# Scheda_analogica.net
KiCad netlist of a schematic drawn in EAGLE
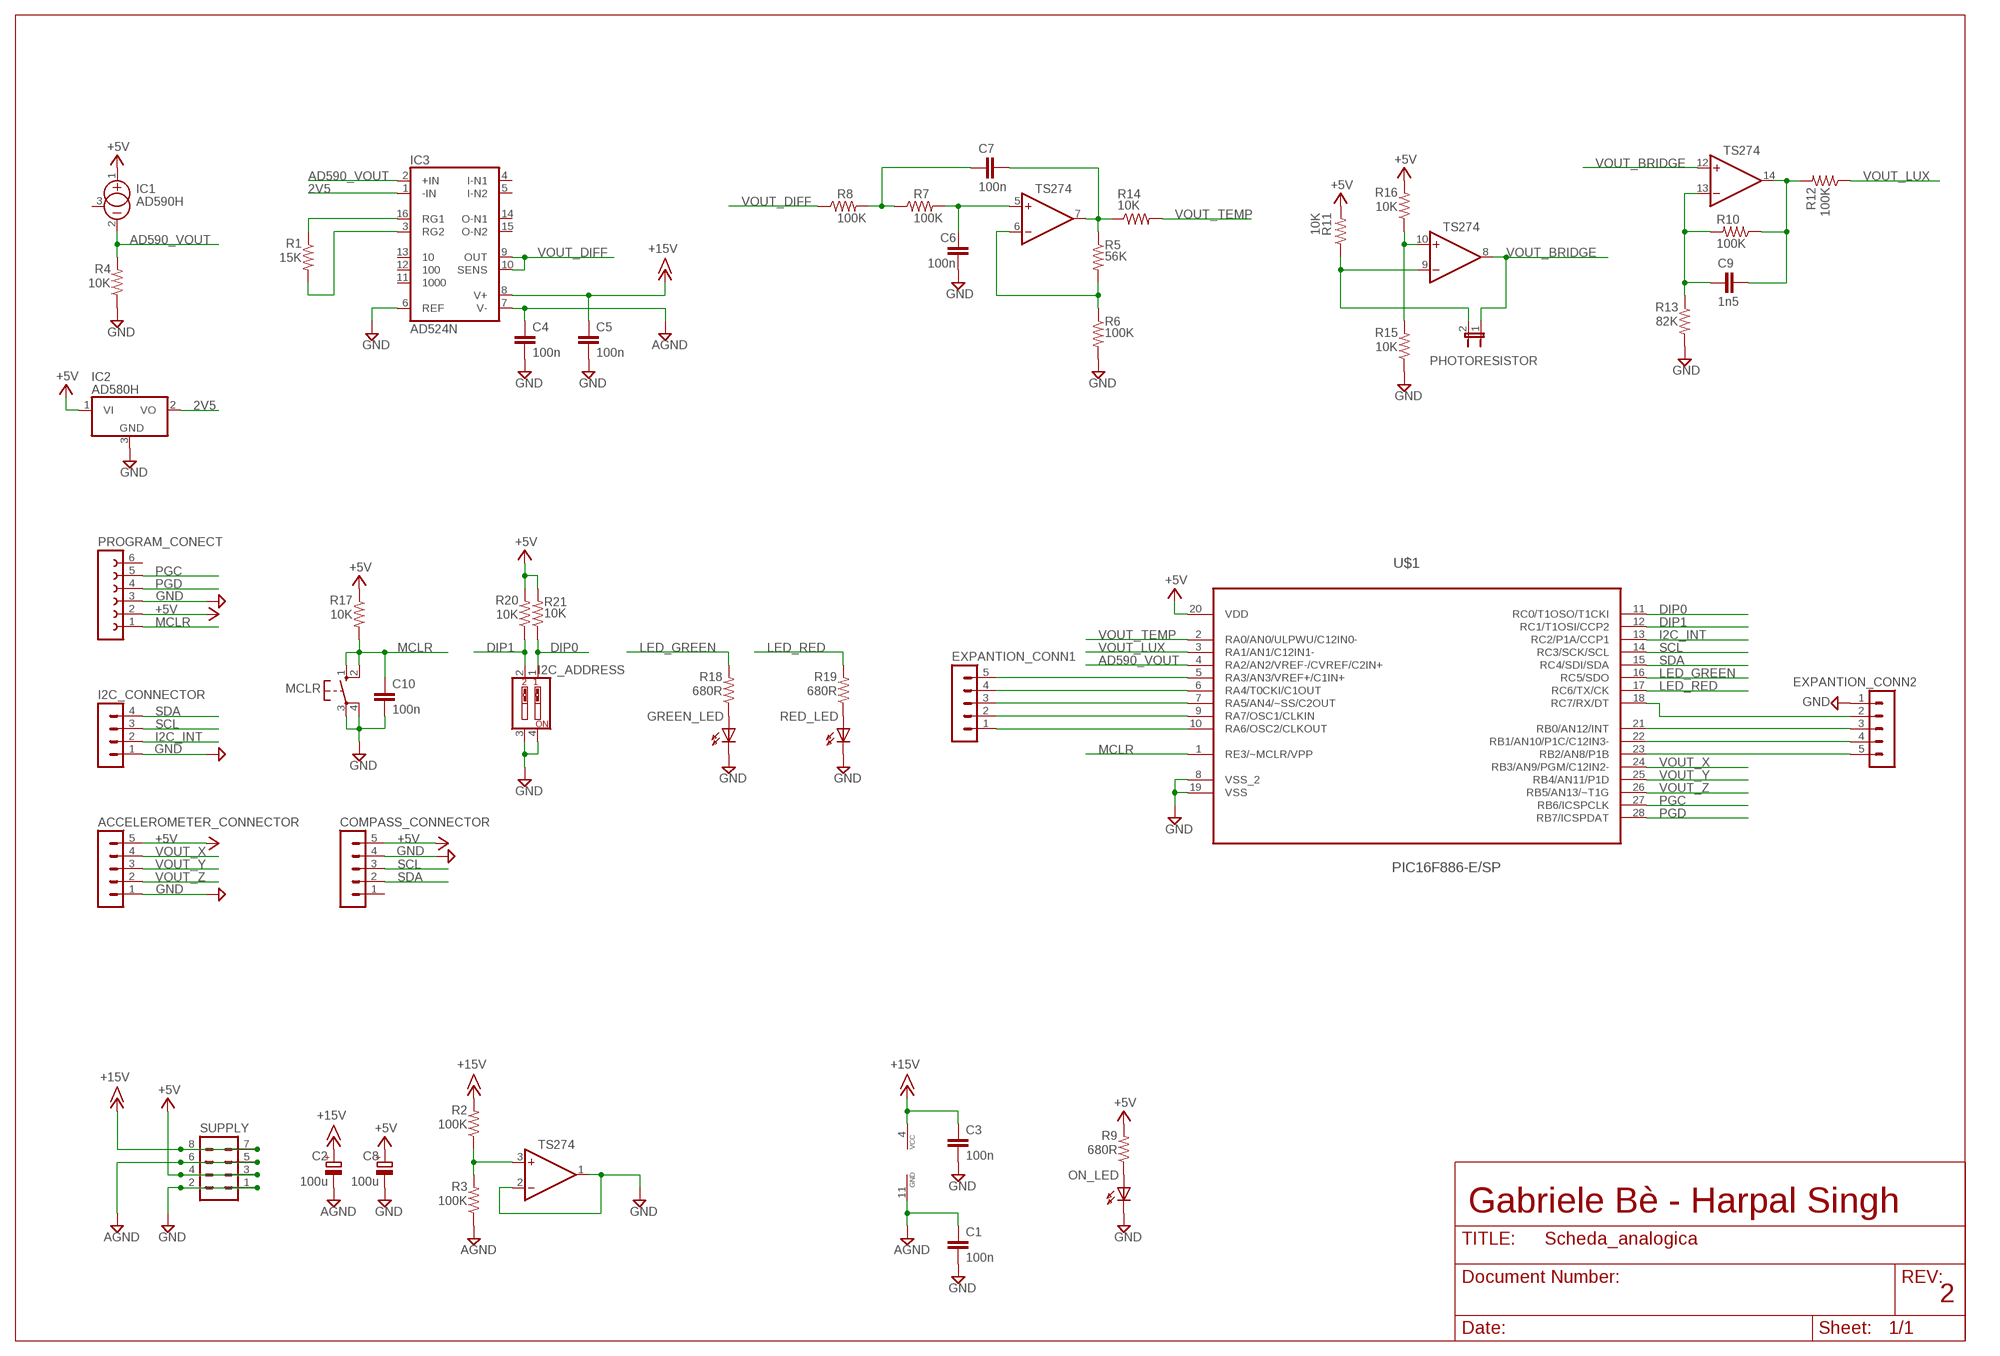
[diagram p0: schematic, sheet 1]

(export (version "E")
  (design (tool "Eeschema 10.0.6"))
  (components
    (comp (ref "ACCELEROMETER_CONNECTOR")
      (value "MA05-1")
      (footprint "eagle-import:MA05-1")
      (libsource (lib "eagle-import") (part "MA05-1"))
    )
    (comp (ref "C1")
      (value "100n")
      (footprint "eagle-import:C050-024X044")
      (libsource (lib "eagle-import") (part "C-EU050-024X044"))
    )
    (comp (ref "C2")
      (value "100u")
      (footprint "eagle-import:E2,5-7")
      (libsource (lib "eagle-import") (part "CPOL-EUE2.5-7"))
    )
    (comp (ref "C3")
      (value "100n")
      (footprint "eagle-import:C050-024X044")
      (libsource (lib "eagle-import") (part "C-EU050-024X044"))
    )
    (comp (ref "C4")
      (value "100n")
      (footprint "eagle-import:C050-024X044")
      (libsource (lib "eagle-import") (part "C-EU050-024X044"))
    )
    (comp (ref "C5")
      (value "100n")
      (footprint "eagle-import:C050-024X044")
      (libsource (lib "eagle-import") (part "C-EU050-024X044"))
    )
    (comp (ref "C6")
      (value "100n")
      (footprint "eagle-import:C050-024X044")
      (libsource (lib "eagle-import") (part "C-EU050-024X044"))
    )
    (comp (ref "C7")
      (value "100n")
      (footprint "eagle-import:C050-024X044")
      (libsource (lib "eagle-import") (part "C-EU050-024X044"))
    )
    (comp (ref "C8")
      (value "100u")
      (footprint "eagle-import:E2,5-7")
      (libsource (lib "eagle-import") (part "CPOL-EUE2.5-7"))
    )
    (comp (ref "C9")
      (value "1n5")
      (footprint "eagle-import:C050-024X044")
      (libsource (lib "eagle-import") (part "C-EU050-024X044"))
    )
    (comp (ref "C10")
      (value "100n")
      (footprint "eagle-import:C050-024X044")
      (libsource (lib "eagle-import") (part "C-EU050-024X044"))
    )
    (comp (ref "COMPASS_CONNECTOR")
      (value "MA05-1")
      (footprint "eagle-import:MA05-1")
      (libsource (lib "eagle-import") (part "MA05-1"))
    )
    (comp (ref "EXPANTION_CONN1")
      (value "MA05-1")
      (footprint "eagle-import:MA05-1")
      (libsource (lib "eagle-import") (part "MA05-1"))
    )
    (comp (ref "EXPANTION_CONN2")
      (value "MA05-1")
      (footprint "eagle-import:MA05-1")
      (libsource (lib "eagle-import") (part "MA05-1"))
    )
    (comp (ref "GREEN_LED")
      (value "HLMP6")
      (footprint "eagle-import:HLMP6")
      (fields (field (name "MF") "AGILENT TECHNOLOGIES") (field (name "MPN") "HLMP-6500"))
      (libsource (lib "eagle-import") (part "HLMP6"))
    )
    (comp (ref "I2C_ADDRESS")
      (value "SW_DIP-2")
      (footprint "eagle-import:EDG-02")
      (libsource (lib "eagle-import") (part "SW_DIP-2"))
    )
    (comp (ref "I2C_CONNECTOR")
      (value "MA04-1")
      (footprint "eagle-import:MA04-1")
      (libsource (lib "eagle-import") (part "MA04-1"))
    )
    (comp (ref "IC1")
      (value "AD590H")
      (footprint "eagle-import:TO18")
      (libsource (lib "eagle-import") (part "AD590H"))
    )
    (comp (ref "IC2")
      (value "AD580H")
      (footprint "eagle-import:TO39")
      (libsource (lib "eagle-import") (part "AD580H"))
    )
    (comp (ref "IC3")
      (value "AD524N")
      (footprint "eagle-import:DIL16")
      (libsource (lib "eagle-import") (part "AD524N"))
    )
    (comp (ref "IC4")
      (value "TS274")
      (footprint "eagle-import:DIL14")
      (libsource (lib "eagle-import") (part "TS274"))
    )
    (comp (ref "MCLR")
      (value "10-XX")
      (footprint "eagle-import:B3F-10XX")
      (libsource (lib "eagle-import") (part "10-XX"))
    )
    (comp (ref "ON_LED")
      (value "HLMP6")
      (footprint "eagle-import:HLMP6")
      (fields (field (name "MF") "AGILENT TECHNOLOGIES") (field (name "MPN") "HLMP-6500"))
      (libsource (lib "eagle-import") (part "HLMP6"))
    )
    (comp (ref "PHOTORESISTOR")
      (value "JP1E")
      (footprint "eagle-import:JP1")
      (libsource (lib "eagle-import") (part "JP1E"))
    )
    (comp (ref "PROGRAM_CONECT")
      (value "FE06-1")
      (footprint "eagle-import:FE06")
      (libsource (lib "eagle-import") (part "FE06-1"))
    )
    (comp (ref "R1")
      (value "15K")
      (footprint "eagle-import:0207_10")
      (libsource (lib "eagle-import") (part "R-US_0207/10"))
    )
    (comp (ref "R2")
      (value "100K")
      (footprint "eagle-import:0207_10")
      (libsource (lib "eagle-import") (part "R-US_0207/10"))
    )
    (comp (ref "R3")
      (value "100K")
      (footprint "eagle-import:0207_10")
      (libsource (lib "eagle-import") (part "R-US_0207/10"))
    )
    (comp (ref "R4")
      (value "10K")
      (footprint "eagle-import:0207_10")
      (libsource (lib "eagle-import") (part "R-US_0207/10"))
    )
    (comp (ref "R5")
      (value "56K")
      (footprint "eagle-import:0207_10")
      (libsource (lib "eagle-import") (part "R-US_0207/10"))
    )
    (comp (ref "R6")
      (value "100K")
      (footprint "eagle-import:0207_10")
      (libsource (lib "eagle-import") (part "R-US_0207/10"))
    )
    (comp (ref "R7")
      (value "100K")
      (footprint "eagle-import:0207_10")
      (libsource (lib "eagle-import") (part "R-US_0207/10"))
    )
    (comp (ref "R8")
      (value "100K")
      (footprint "eagle-import:0207_10")
      (libsource (lib "eagle-import") (part "R-US_0207/10"))
    )
    (comp (ref "R9")
      (value "680R")
      (footprint "eagle-import:0207_10")
      (libsource (lib "eagle-import") (part "R-US_0207/10"))
    )
    (comp (ref "R10")
      (value "100K")
      (footprint "eagle-import:0207_10")
      (libsource (lib "eagle-import") (part "R-US_0207/10"))
    )
    (comp (ref "R11")
      (value "10K")
      (footprint "eagle-import:0207_10")
      (libsource (lib "eagle-import") (part "R-US_0207/10"))
    )
    (comp (ref "R12")
      (value "100K")
      (footprint "eagle-import:0207_10")
      (libsource (lib "eagle-import") (part "R-US_0207/10"))
    )
    (comp (ref "R13")
      (value "82K")
      (footprint "eagle-import:0207_10")
      (libsource (lib "eagle-import") (part "R-US_0207/10"))
    )
    (comp (ref "R14")
      (value "10K")
      (footprint "eagle-import:0207_10")
      (libsource (lib "eagle-import") (part "R-US_0207/10"))
    )
    (comp (ref "R15")
      (value "10K")
      (footprint "eagle-import:0207_10")
      (libsource (lib "eagle-import") (part "R-US_0207/10"))
    )
    (comp (ref "R16")
      (value "10K")
      (footprint "eagle-import:0207_10")
      (libsource (lib "eagle-import") (part "R-US_0207/10"))
    )
    (comp (ref "R17")
      (value "10K")
      (footprint "eagle-import:0207_10")
      (libsource (lib "eagle-import") (part "R-US_0207/10"))
    )
    (comp (ref "R18")
      (value "680R")
      (footprint "eagle-import:0207_10")
      (libsource (lib "eagle-import") (part "R-US_0207/10"))
    )
    (comp (ref "R19")
      (value "680R")
      (footprint "eagle-import:0207_10")
      (libsource (lib "eagle-import") (part "R-US_0207/10"))
    )
    (comp (ref "R20")
      (value "10K")
      (footprint "eagle-import:0207_10")
      (libsource (lib "eagle-import") (part "R-US_0207/10"))
    )
    (comp (ref "R21")
      (value "10K")
      (footprint "eagle-import:0207_10")
      (libsource (lib "eagle-import") (part "R-US_0207/10"))
    )
    (comp (ref "RED_LED")
      (value "HLMP6")
      (footprint "eagle-import:HLMP6")
      (fields (field (name "MF") "AGILENT TECHNOLOGIES") (field (name "MPN") "HLMP-6500"))
      (libsource (lib "eagle-import") (part "HLMP6"))
    )
    (comp (ref "SUPPLY")
      (value "MA04-2")
      (footprint "eagle-import:MA04-2")
      (libsource (lib "eagle-import") (part "MA04-2"))
    )
    (comp (ref "U$1")
      (value "PIC16F886-E/SP")
      (footprint "eagle-import:DIP254P762X508-28")
      (libsource (lib "eagle-import") (part "PIC16F886-E/SP"))
    )
  )
  (nets
    (net (code "1") (name "+5V") (class "Default")
      (node (ref "ACCELEROMETER_CONNECTOR") (pin "5") (pinfunction "5_5") (pintype "passive"))
      (node (ref "C8") (pin "+") (pinfunction "+_+") (pintype "passive"))
      (node (ref "COMPASS_CONNECTOR") (pin "5") (pinfunction "5_5") (pintype "passive"))
      (node (ref "IC1") (pin "1") (pinfunction "+_1") (pintype "input"))
      (node (ref "IC2") (pin "1") (pinfunction "VI_1") (pintype "input"))
      (node (ref "PROGRAM_CONECT") (pin "2") (pinfunction "2_2") (pintype "passive"))
      (node (ref "R11") (pin "2") (pinfunction "2_2") (pintype "passive"))
      (node (ref "R16") (pin "2") (pinfunction "2_2") (pintype "passive"))
      (node (ref "R17") (pin "1") (pinfunction "1_1") (pintype "passive"))
      (node (ref "R20") (pin "2") (pinfunction "2_2") (pintype "passive"))
      (node (ref "R21") (pin "2") (pinfunction "2_2") (pintype "passive"))
      (node (ref "R9") (pin "2") (pinfunction "2_2") (pintype "passive"))
      (node (ref "SUPPLY") (pin "3") (pinfunction "3_3") (pintype "passive"))
      (node (ref "SUPPLY") (pin "4") (pinfunction "4_4") (pintype "passive"))
      (node (ref "U$1") (pin "20") (pinfunction "VDD_20") (pintype "power_in"))
    )
    (net (code "2") (name "+15V") (class "Default")
      (node (ref "C2") (pin "+") (pinfunction "+_+") (pintype "passive"))
      (node (ref "C3") (pin "1") (pinfunction "1_1") (pintype "passive"))
      (node (ref "C5") (pin "1") (pinfunction "1_1") (pintype "passive"))
      (node (ref "IC3") (pin "8") (pinfunction "V+_8") (pintype "power_in"))
      (node (ref "IC4") (pin "4") (pinfunction "VCC_4") (pintype "power_in"))
      (node (ref "R2") (pin "2") (pinfunction "2_2") (pintype "passive"))
      (node (ref "SUPPLY") (pin "7") (pinfunction "7_7") (pintype "passive"))
      (node (ref "SUPPLY") (pin "8") (pinfunction "8_8") (pintype "passive"))
    )
    (net (code "3") (name "/2V5") (class "Default")
      (node (ref "IC2") (pin "2") (pinfunction "VO_2") (pintype "passive"))
      (node (ref "IC3") (pin "1") (pinfunction "-IN_1") (pintype "input"))
    )
    (net (code "4") (name "/AD590_VOUT") (class "Default")
      (node (ref "IC1") (pin "2") (pinfunction "-_2") (pintype "input"))
      (node (ref "IC3") (pin "2") (pinfunction "+IN_2") (pintype "input"))
      (node (ref "R4") (pin "2") (pinfunction "2_2") (pintype "passive"))
      (node (ref "U$1") (pin "4") (pinfunction "RA2/AN2/VREF-/CVREF/C2IN+_4") (pintype "bidirectional"))
    )
    (net (code "5") (name "/DIP0") (class "Default")
      (node (ref "I2C_ADDRESS") (pin "1") (pinfunction "1_1") (pintype "passive"))
      (node (ref "R21") (pin "1") (pinfunction "1_1") (pintype "passive"))
      (node (ref "U$1") (pin "11") (pinfunction "RC0/T1OSO/T1CKI_11") (pintype "bidirectional"))
    )
    (net (code "6") (name "/DIP1") (class "Default")
      (node (ref "I2C_ADDRESS") (pin "2") (pinfunction "2_2") (pintype "passive"))
      (node (ref "R20") (pin "1") (pinfunction "1_1") (pintype "passive"))
      (node (ref "U$1") (pin "12") (pinfunction "RC1/T1OSI/CCP2_12") (pintype "bidirectional"))
    )
    (net (code "7") (name "/I2C_INT") (class "Default")
      (node (ref "I2C_CONNECTOR") (pin "2") (pinfunction "2_2") (pintype "passive"))
      (node (ref "U$1") (pin "13") (pinfunction "RC2/P1A/CCP1_13") (pintype "bidirectional"))
    )
    (net (code "8") (name "/LED_GREEN") (class "Default")
      (node (ref "R18") (pin "2") (pinfunction "2_2") (pintype "passive"))
      (node (ref "U$1") (pin "16") (pinfunction "RC5/SDO_16") (pintype "bidirectional"))
    )
    (net (code "9") (name "/LED_RED") (class "Default")
      (node (ref "R19") (pin "2") (pinfunction "2_2") (pintype "passive"))
      (node (ref "U$1") (pin "17") (pinfunction "RC6/TX/CK_17") (pintype "bidirectional"))
    )
    (net (code "10") (name "/MCLR") (class "Default")
      (node (ref "C10") (pin "1") (pinfunction "1_1") (pintype "passive"))
      (node (ref "MCLR") (pin "1") (pinfunction "S_1") (pintype "passive"))
      (node (ref "MCLR") (pin "2") (pinfunction "S1_2") (pintype "passive"))
      (node (ref "PROGRAM_CONECT") (pin "1") (pinfunction "1_1") (pintype "passive"))
      (node (ref "R17") (pin "2") (pinfunction "2_2") (pintype "passive"))
      (node (ref "U$1") (pin "1") (pinfunction "RE3/~{MCLR/VPP}_1") (pintype "input"))
    )
    (net (code "11") (name "/PGC") (class "Default")
      (node (ref "PROGRAM_CONECT") (pin "5") (pinfunction "5_5") (pintype "passive"))
      (node (ref "U$1") (pin "27") (pinfunction "RB6/ICSPCLK_27") (pintype "bidirectional"))
    )
    (net (code "12") (name "/PGD") (class "Default")
      (node (ref "PROGRAM_CONECT") (pin "4") (pinfunction "4_4") (pintype "passive"))
      (node (ref "U$1") (pin "28") (pinfunction "RB7/ICSPDAT_28") (pintype "bidirectional"))
    )
    (net (code "13") (name "/SCL") (class "Default")
      (node (ref "COMPASS_CONNECTOR") (pin "3") (pinfunction "3_3") (pintype "passive"))
      (node (ref "I2C_CONNECTOR") (pin "3") (pinfunction "3_3") (pintype "passive"))
      (node (ref "U$1") (pin "14") (pinfunction "RC3/SCK/SCL_14") (pintype "bidirectional"))
    )
    (net (code "14") (name "/SDA") (class "Default")
      (node (ref "COMPASS_CONNECTOR") (pin "2") (pinfunction "2_2") (pintype "passive"))
      (node (ref "I2C_CONNECTOR") (pin "4") (pinfunction "4_4") (pintype "passive"))
      (node (ref "U$1") (pin "15") (pinfunction "RC4/SDI/SDA_15") (pintype "bidirectional"))
    )
    (net (code "15") (name "/VOUT_BRIDGE") (class "Default")
      (node (ref "IC4") (pin "12") (pinfunction "+IN_12") (pintype "input"))
      (node (ref "IC4") (pin "8") (pinfunction "OUT_8") (pintype "output"))
      (node (ref "PHOTORESISTOR") (pin "1") (pinfunction "1_1") (pintype "passive"))
    )
    (net (code "16") (name "/VOUT_DIFF") (class "Default")
      (node (ref "IC3") (pin "10") (pinfunction "SENS_10") (pintype "input"))
      (node (ref "IC3") (pin "9") (pinfunction "OUT_9") (pintype "output"))
      (node (ref "R8") (pin "1") (pinfunction "1_1") (pintype "passive"))
    )
    (net (code "17") (name "/VOUT_LUX") (class "Default")
      (node (ref "R12") (pin "1") (pinfunction "1_1") (pintype "passive"))
      (node (ref "U$1") (pin "3") (pinfunction "RA1/AN1/C12IN1-_3") (pintype "bidirectional"))
    )
    (net (code "18") (name "/VOUT_TEMP") (class "Default")
      (node (ref "R14") (pin "2") (pinfunction "2_2") (pintype "passive"))
      (node (ref "U$1") (pin "2") (pinfunction "RA0/AN0/ULPWU/C12IN0-_2") (pintype "bidirectional"))
    )
    (net (code "19") (name "/VOUT_X") (class "Default")
      (node (ref "ACCELEROMETER_CONNECTOR") (pin "4") (pinfunction "4_4") (pintype "passive"))
      (node (ref "U$1") (pin "24") (pinfunction "RB3/AN9/PGM/C12IN2-_24") (pintype "bidirectional"))
    )
    (net (code "20") (name "/VOUT_Y") (class "Default")
      (node (ref "ACCELEROMETER_CONNECTOR") (pin "3") (pinfunction "3_3") (pintype "passive"))
      (node (ref "U$1") (pin "25") (pinfunction "RB4/AN11/P1D_25") (pintype "bidirectional"))
    )
    (net (code "21") (name "/VOUT_Z") (class "Default")
      (node (ref "ACCELEROMETER_CONNECTOR") (pin "2") (pinfunction "2_2") (pintype "passive"))
      (node (ref "U$1") (pin "26") (pinfunction "RB5/AN13/~{T1G}_26") (pintype "bidirectional"))
    )
    (net (code "22") (name "AGND") (class "Default")
      (node (ref "C1") (pin "1") (pinfunction "1_1") (pintype "passive"))
      (node (ref "C2") (pin "-") (pinfunction "-_-") (pintype "passive"))
      (node (ref "C4") (pin "1") (pinfunction "1_1") (pintype "passive"))
      (node (ref "IC3") (pin "7") (pinfunction "V-_7") (pintype "power_in"))
      (node (ref "IC4") (pin "11") (pinfunction "GND_11") (pintype "power_in"))
      (node (ref "R3") (pin "1") (pinfunction "1_1") (pintype "passive"))
      (node (ref "SUPPLY") (pin "5") (pinfunction "5_5") (pintype "passive"))
      (node (ref "SUPPLY") (pin "6") (pinfunction "6_6") (pintype "passive"))
    )
    (net (code "23") (name "GND") (class "Default")
      (node (ref "ACCELEROMETER_CONNECTOR") (pin "1") (pinfunction "1_1") (pintype "passive"))
      (node (ref "C1") (pin "2") (pinfunction "2_2") (pintype "passive"))
      (node (ref "C10") (pin "2") (pinfunction "2_2") (pintype "passive"))
      (node (ref "C3") (pin "2") (pinfunction "2_2") (pintype "passive"))
      (node (ref "C4") (pin "2") (pinfunction "2_2") (pintype "passive"))
      (node (ref "C5") (pin "2") (pinfunction "2_2") (pintype "passive"))
      (node (ref "C6") (pin "2") (pinfunction "2_2") (pintype "passive"))
      (node (ref "C8") (pin "-") (pinfunction "-_-") (pintype "passive"))
      (node (ref "COMPASS_CONNECTOR") (pin "4") (pinfunction "4_4") (pintype "passive"))
      (node (ref "EXPANTION_CONN2") (pin "1") (pinfunction "1_1") (pintype "passive"))
      (node (ref "GREEN_LED") (pin "K") (pinfunction "K_K") (pintype "passive"))
      (node (ref "I2C_ADDRESS") (pin "3") (pinfunction "3_3") (pintype "passive"))
      (node (ref "I2C_ADDRESS") (pin "4") (pinfunction "4_4") (pintype "passive"))
      (node (ref "I2C_CONNECTOR") (pin "1") (pinfunction "1_1") (pintype "passive"))
      (node (ref "IC2") (pin "3") (pinfunction "GND_3") (pintype "passive"))
      (node (ref "IC3") (pin "6") (pinfunction "REF_6") (pintype "input"))
      (node (ref "IC4") (pin "1") (pinfunction "OUT_1") (pintype "output"))
      (node (ref "IC4") (pin "2") (pinfunction "-IN_2") (pintype "input"))
      (node (ref "MCLR") (pin "3") (pinfunction "P_3") (pintype "passive"))
      (node (ref "MCLR") (pin "4") (pinfunction "P1_4") (pintype "passive"))
      (node (ref "ON_LED") (pin "K") (pinfunction "K_K") (pintype "passive"))
      (node (ref "PROGRAM_CONECT") (pin "3") (pinfunction "3_3") (pintype "passive"))
      (node (ref "R13") (pin "2") (pinfunction "2_2") (pintype "passive"))
      (node (ref "R15") (pin "1") (pinfunction "1_1") (pintype "passive"))
      (node (ref "R4") (pin "1") (pinfunction "1_1") (pintype "passive"))
      (node (ref "R6") (pin "2") (pinfunction "2_2") (pintype "passive"))
      (node (ref "RED_LED") (pin "K") (pinfunction "K_K") (pintype "passive"))
      (node (ref "SUPPLY") (pin "1") (pinfunction "1_1") (pintype "passive"))
      (node (ref "SUPPLY") (pin "2") (pinfunction "2_2") (pintype "passive"))
      (node (ref "U$1") (pin "19") (pinfunction "VSS_19") (pintype "passive"))
      (node (ref "U$1") (pin "8") (pinfunction "VSS_2_8") (pintype "passive"))
    )
    (net (code "24") (name "Net-(C7-Pad1)") (class "Default")
      (node (ref "C7") (pin "1") (pinfunction "1_1") (pintype "passive"))
      (node (ref "R7") (pin "1") (pinfunction "1_1") (pintype "passive"))
      (node (ref "R8") (pin "2") (pinfunction "2_2") (pintype "passive"))
    )
    (net (code "25") (name "Net-(GREEN_LED-PadA)") (class "Default")
      (node (ref "GREEN_LED") (pin "A") (pinfunction "A_A") (pintype "passive"))
      (node (ref "R18") (pin "1") (pinfunction "1_1") (pintype "passive"))
    )
    (net (code "26") (name "Net-(IC3-RG1)") (class "Default")
      (node (ref "IC3") (pin "16") (pinfunction "RG1_16") (pintype "passive"))
      (node (ref "R1") (pin "1") (pinfunction "1_1") (pintype "passive"))
    )
    (net (code "27") (name "Net-(IC3-RG2)") (class "Default")
      (node (ref "IC3") (pin "3") (pinfunction "RG2_3") (pintype "passive"))
      (node (ref "R1") (pin "2") (pinfunction "2_2") (pintype "passive"))
    )
    (net (code "28") (name "Net-(IC4A-+IN)") (class "Default")
      (node (ref "IC4") (pin "3") (pinfunction "+IN_3") (pintype "input"))
      (node (ref "R2") (pin "1") (pinfunction "1_1") (pintype "passive"))
      (node (ref "R3") (pin "2") (pinfunction "2_2") (pintype "passive"))
    )
    (net (code "29") (name "Net-(IC4B-+IN)") (class "Default")
      (node (ref "C6") (pin "1") (pinfunction "1_1") (pintype "passive"))
      (node (ref "IC4") (pin "5") (pinfunction "+IN_5") (pintype "input"))
      (node (ref "R7") (pin "2") (pinfunction "2_2") (pintype "passive"))
    )
    (net (code "30") (name "Net-(IC4B--IN)") (class "Default")
      (node (ref "IC4") (pin "6") (pinfunction "-IN_6") (pintype "input"))
      (node (ref "R5") (pin "2") (pinfunction "2_2") (pintype "passive"))
      (node (ref "R6") (pin "1") (pinfunction "1_1") (pintype "passive"))
    )
    (net (code "31") (name "Net-(IC4B-OUT)") (class "Default")
      (node (ref "C7") (pin "2") (pinfunction "2_2") (pintype "passive"))
      (node (ref "IC4") (pin "7") (pinfunction "OUT_7") (pintype "output"))
      (node (ref "R14") (pin "1") (pinfunction "1_1") (pintype "passive"))
      (node (ref "R5") (pin "1") (pinfunction "1_1") (pintype "passive"))
    )
    (net (code "32") (name "Net-(IC4C-+IN)") (class "Default")
      (node (ref "IC4") (pin "10") (pinfunction "+IN_10") (pintype "input"))
      (node (ref "R15") (pin "2") (pinfunction "2_2") (pintype "passive"))
      (node (ref "R16") (pin "1") (pinfunction "1_1") (pintype "passive"))
    )
    (net (code "33") (name "Net-(IC4C--IN)") (class "Default")
      (node (ref "IC4") (pin "9") (pinfunction "-IN_9") (pintype "input"))
      (node (ref "PHOTORESISTOR") (pin "2") (pinfunction "2_2") (pintype "passive"))
      (node (ref "R11") (pin "1") (pinfunction "1_1") (pintype "passive"))
    )
    (net (code "34") (name "Net-(IC4D--IN)") (class "Default")
      (node (ref "C9") (pin "1") (pinfunction "1_1") (pintype "passive"))
      (node (ref "IC4") (pin "13") (pinfunction "-IN_13") (pintype "input"))
      (node (ref "R10") (pin "2") (pinfunction "2_2") (pintype "passive"))
      (node (ref "R13") (pin "1") (pinfunction "1_1") (pintype "passive"))
    )
    (net (code "35") (name "Net-(IC4D-OUT)") (class "Default")
      (node (ref "C9") (pin "2") (pinfunction "2_2") (pintype "passive"))
      (node (ref "IC4") (pin "14") (pinfunction "OUT_14") (pintype "output"))
      (node (ref "R10") (pin "1") (pinfunction "1_1") (pintype "passive"))
      (node (ref "R12") (pin "2") (pinfunction "2_2") (pintype "passive"))
    )
    (net (code "36") (name "Net-(ON_LED-PadA)") (class "Default")
      (node (ref "ON_LED") (pin "A") (pinfunction "A_A") (pintype "passive"))
      (node (ref "R9") (pin "1") (pinfunction "1_1") (pintype "passive"))
    )
    (net (code "37") (name "Net-(R19-Pad1)") (class "Default")
      (node (ref "R19") (pin "1") (pinfunction "1_1") (pintype "passive"))
      (node (ref "RED_LED") (pin "A") (pinfunction "A_A") (pintype "passive"))
    )
    (net (code "38") (name "Net-(U$1-RA3{slash}AN3{slash}VREF+{slash}C1IN+)") (class "Default")
      (node (ref "EXPANTION_CONN1") (pin "5") (pinfunction "5_5") (pintype "passive"))
      (node (ref "U$1") (pin "5") (pinfunction "RA3/AN3/VREF+/C1IN+_5") (pintype "bidirectional"))
    )
    (net (code "39") (name "Net-(U$1-RA4{slash}T0CKI{slash}C1OUT)") (class "Default")
      (node (ref "EXPANTION_CONN1") (pin "4") (pinfunction "4_4") (pintype "passive"))
      (node (ref "U$1") (pin "6") (pinfunction "RA4/T0CKI/C1OUT_6") (pintype "bidirectional"))
    )
    (net (code "40") (name "Net-(U$1-RA5{slash}AN4{slash}~{SS{slash}C2OUT})") (class "Default")
      (node (ref "EXPANTION_CONN1") (pin "3") (pinfunction "3_3") (pintype "passive"))
      (node (ref "U$1") (pin "7") (pinfunction "RA5/AN4/~{SS/C2OUT}_7") (pintype "bidirectional"))
    )
    (net (code "41") (name "Net-(U$1-RA6{slash}OSC2{slash}CLKOUT)") (class "Default")
      (node (ref "EXPANTION_CONN1") (pin "1") (pinfunction "1_1") (pintype "passive"))
      (node (ref "U$1") (pin "10") (pinfunction "RA6/OSC2/CLKOUT_10") (pintype "bidirectional"))
    )
    (net (code "42") (name "Net-(U$1-RA7{slash}OSC1{slash}CLKIN)") (class "Default")
      (node (ref "EXPANTION_CONN1") (pin "2") (pinfunction "2_2") (pintype "passive"))
      (node (ref "U$1") (pin "9") (pinfunction "RA7/OSC1/CLKIN_9") (pintype "bidirectional"))
    )
    (net (code "43") (name "Net-(U$1-RB0{slash}AN12{slash}INT)") (class "Default")
      (node (ref "EXPANTION_CONN2") (pin "3") (pinfunction "3_3") (pintype "passive"))
      (node (ref "U$1") (pin "21") (pinfunction "RB0/AN12/INT_21") (pintype "bidirectional"))
    )
    (net (code "44") (name "Net-(U$1-RB1{slash}AN10{slash}P1C{slash}C12IN3-)") (class "Default")
      (node (ref "EXPANTION_CONN2") (pin "4") (pinfunction "4_4") (pintype "passive"))
      (node (ref "U$1") (pin "22") (pinfunction "RB1/AN10/P1C/C12IN3-_22") (pintype "bidirectional"))
    )
    (net (code "45") (name "Net-(U$1-RB2{slash}AN8{slash}P1B)") (class "Default")
      (node (ref "EXPANTION_CONN2") (pin "5") (pinfunction "5_5") (pintype "passive"))
      (node (ref "U$1") (pin "23") (pinfunction "RB2/AN8/P1B_23") (pintype "bidirectional"))
    )
    (net (code "46") (name "Net-(U$1-RC7{slash}RX{slash}DT)") (class "Default")
      (node (ref "EXPANTION_CONN2") (pin "2") (pinfunction "2_2") (pintype "passive"))
      (node (ref "U$1") (pin "18") (pinfunction "RC7/RX/DT_18") (pintype "bidirectional"))
    )
    (net (code "47") (name "unconnected-(COMPASS_CONNECTOR-Pad1)") (class "Default")
      (node (ref "COMPASS_CONNECTOR") (pin "1") (pinfunction "1_1") (pintype "passive"))
    )
    (net (code "48") (name "unconnected-(IC1-CAN-Pad3)") (class "Default")
      (node (ref "IC1") (pin "3") (pinfunction "CAN_3") (pintype "passive"))
    )
    (net (code "49") (name "unconnected-(IC3-10-Pad13)") (class "Default")
      (node (ref "IC3") (pin "13") (pinfunction "10_13") (pintype "output"))
    )
    (net (code "50") (name "unconnected-(IC3-100-Pad12)") (class "Default")
      (node (ref "IC3") (pin "12") (pinfunction "100_12") (pintype "output"))
    )
    (net (code "51") (name "unconnected-(IC3-1000-Pad11)") (class "Default")
      (node (ref "IC3") (pin "11") (pinfunction "1000_11") (pintype "output"))
    )
    (net (code "52") (name "unconnected-(IC3-I-N1-Pad4)") (class "Default")
      (node (ref "IC3") (pin "4") (pinfunction "I-N1_4") (pintype "input"))
    )
    (net (code "53") (name "unconnected-(IC3-I-N2-Pad5)") (class "Default")
      (node (ref "IC3") (pin "5") (pinfunction "I-N2_5") (pintype "input"))
    )
    (net (code "54") (name "unconnected-(IC3-O-N1-Pad14)") (class "Default")
      (node (ref "IC3") (pin "14") (pinfunction "O-N1_14") (pintype "input"))
    )
    (net (code "55") (name "unconnected-(IC3-O-N2-Pad15)") (class "Default")
      (node (ref "IC3") (pin "15") (pinfunction "O-N2_15") (pintype "input"))
    )
    (net (code "56") (name "unconnected-(PROGRAM_CONECT-Pad6)") (class "Default")
      (node (ref "PROGRAM_CONECT") (pin "6") (pinfunction "6_6") (pintype "passive"))
    )
  )
)
